# USB.net
KiCad netlist of a schematic drawn in Altium Designer
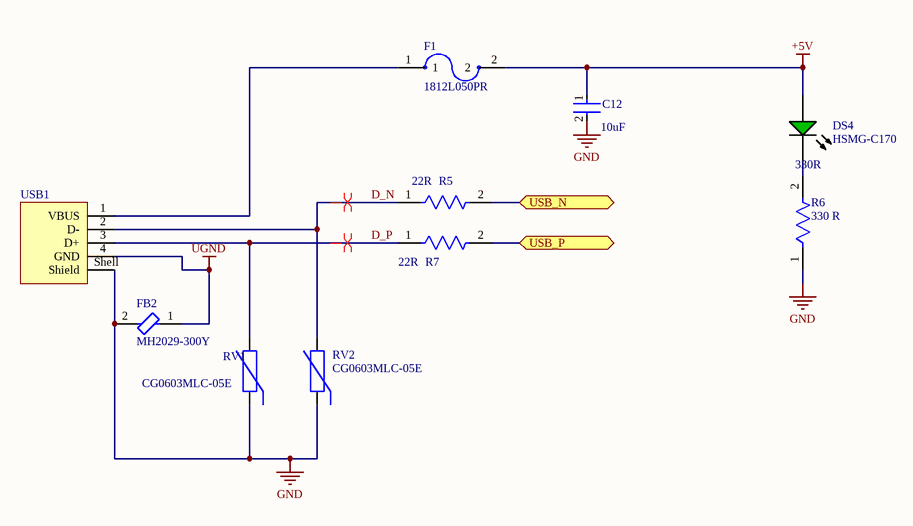
[diagram p0: USB.SchDoc]

(export (version "E")
  (design (tool "Eeschema 10.0.6"))
  (components
    (comp (ref "C12")
      (value "C0805C106K8PACTU")
      (footprint "FP-C0805C-DG-MFG")
      (description "CAP CER 10UF 10V X5R 0805")
      (fields
        (field (name "TOLERANCE") "10%")
        (field (name "MANUFACTURER") "Kemet")
        (field (name "CAPACITANCE") "10uF")
      )
      (libsource (lib "Altium Content Vault") (part "11868f565c42a9108669ba33697ecf6"))
    )
    (comp (ref "DS4")
      (value "HSMG-C170")
      (footprint "AVAG-HSMX-C170_V")
      (description "Chip LED, Green, 2.2 V, -40 to 85 degC, 2-Pin SMD, Pb-Free, Tape and Reel")
      (fields (field (name "MANUFACTURER") "Avago"))
      (libsource (lib "Altium Content Vault") (part "LED_GREEN_A1K2-2"))
    )
    (comp (ref "F1")
      (value "1812L050PR")
      (footprint "FUSM4632X75")
      (description "Polymeric PTC Resettable Fuse 15V 500mA Ih Surface Mount 1812 (4532 Metric), Concave")
      (fields (field (name "MF") "Littelfuse Inc."))
      (libsource (lib "University of Moratuwa") (part "1812L050PR"))
    )
    (comp (ref "FB2")
      (value "MH2029-300Y")
      (footprint "FP-MH2029-MFG")
      (description "MH Series High Current Chip Ferrite Beads")
      (fields (field (name "OCTOPART") "https://octopart.com/mh2029-300y-bourns-756929"))
      (libsource (lib "Altium Content Vault") (part "5f30dd21d616792df468990f7003faa"))
    )
    (comp (ref "R5")
      (value "CRCW080522R0FKEA")
      (footprint "FP-CRCW0805-e3-IPC_C")
      (description "RES Thick Film, 22Ω, 1%, 0.125W, 100ppm/°C, 0805")
      (fields (field (name "RESISTANCE") "22R") (field (name "TOLERANCE") "1%"))
      (libsource (lib "Altium Content Vault") (part "1029c3af85768c4190bb7ad29bc67b5"))
    )
    (comp (ref "R6")
      (value "330 R")
      (footprint "FP-CR0805-IPC_B")
      (description "Thick Film Chip Resistors 0805 330Ω 0.125W 1% 100ppm/°C")
      (fields (field (name "TOLERANCE") "1%") (field (name "RESISTANCE") "330R"))
      (libsource (lib "Altium Content Vault") (part "1029c3af85768c4190bb7ad29bc67b5"))
    )
    (comp (ref "R7")
      (value "CRCW080522R0FKEA")
      (footprint "FP-CRCW0805-e3-IPC_C")
      (description "RES Thick Film, 22Ω, 1%, 0.125W, 100ppm/°C, 0805")
      (fields (field (name "RESISTANCE") "22R") (field (name "TOLERANCE") "1%"))
      (libsource (lib "Altium Content Vault") (part "1029c3af85768c4190bb7ad29bc67b5"))
    )
    (comp (ref "RV1")
      (value "CG0603MLC-05E")
      (footprint "BOUR-CG0603-2_V")
      (description "ESD Protector, 5 V Supply, -40 to 85 degC, 1.6 x 0.8 x 0.55 mm SMD, RoHS, Tape and Reel")
      (fields (field (name "MANUFACTURER") "Bourns"))
      (libsource (lib "Altium Content Vault") (part "BOUR-VSR-2"))
    )
    (comp (ref "RV2")
      (value "CG0603MLC-05E")
      (footprint "BOUR-CG0603-2_V")
      (description "ESD Protector, 5 V Supply, -40 to 85 degC, 1.6 x 0.8 x 0.55 mm SMD, RoHS, Tape and Reel")
      (fields (field (name "MANUFACTURER") "Bourns"))
      (libsource (lib "Altium Content Vault") (part "BOUR-VSR-2"))
    )
    (comp (ref "USB1")
      (value "61400416021")
      (footprint "61400416021")
      (libsource (lib "Altium Content Vault") (part "USB 2.0_Type A_Receptacle_1 Port"))
    )
  )
  (nets
    (net (code "1") (name "+5V") (class "Default")
      (node (ref "C12") (pin "1") (pinfunction "1_1") (pintype "passive"))
      (node (ref "DS4") (pin "1") (pinfunction "A_1") (pintype "passive"))
      (node (ref "F1") (pin "2") (pinfunction "2_2") (pintype "passive"))
    )
    (net (code "2") (name "/D_N") (class "Default")
      (node (ref "R5") (pin "1") (pinfunction "1_1") (pintype "passive"))
      (node (ref "RV2") (pin "2") (pinfunction "2_2") (pintype "passive"))
      (node (ref "USB1") (pin "2") (pinfunction "D-_2") (pintype "passive"))
    )
    (net (code "3") (name "/D_P") (class "Default")
      (node (ref "R7") (pin "1") (pinfunction "1_1") (pintype "passive"))
      (node (ref "RV1") (pin "2") (pinfunction "2_2") (pintype "passive"))
      (node (ref "USB1") (pin "3") (pinfunction "D+_3") (pintype "passive"))
    )
    (net (code "4") (name "/USB_N") (class "Default")
      (node (ref "R5") (pin "2") (pinfunction "2_2") (pintype "passive"))
    )
    (net (code "5") (name "/USB_P") (class "Default")
      (node (ref "R7") (pin "2") (pinfunction "2_2") (pintype "passive"))
    )
    (net (code "6") (name "GND") (class "Default")
      (node (ref "C12") (pin "2") (pinfunction "2_2") (pintype "passive"))
      (node (ref "FB2") (pin "2") (pinfunction "2_2") (pintype "passive"))
      (node (ref "R6") (pin "1") (pinfunction "1_1") (pintype "passive"))
      (node (ref "RV1") (pin "1") (pinfunction "1_1") (pintype "passive"))
      (node (ref "RV2") (pin "1") (pinfunction "1_1") (pintype "passive"))
      (node (ref "USB1") (pin "Shell") (pinfunction "Shield_Shell") (pintype "passive"))
    )
    (net (code "7") (name "Net-(DS4-K)") (class "Default")
      (node (ref "DS4") (pin "2") (pinfunction "K_2") (pintype "passive"))
      (node (ref "R6") (pin "2") (pinfunction "2_2") (pintype "passive"))
    )
    (net (code "8") (name "Net-(USB1-VBUS)") (class "Default")
      (node (ref "F1") (pin "1") (pinfunction "1_1") (pintype "passive"))
      (node (ref "USB1") (pin "1") (pinfunction "VBUS_1") (pintype "passive"))
    )
    (net (code "9") (name "UGND") (class "Default")
      (node (ref "FB2") (pin "1") (pinfunction "1_1") (pintype "passive"))
      (node (ref "USB1") (pin "4") (pinfunction "GND_4") (pintype "passive"))
    )
  )
)
